# omnibothub-power-two.net
KiCad netlist of a schematic drawn in Altium Designer
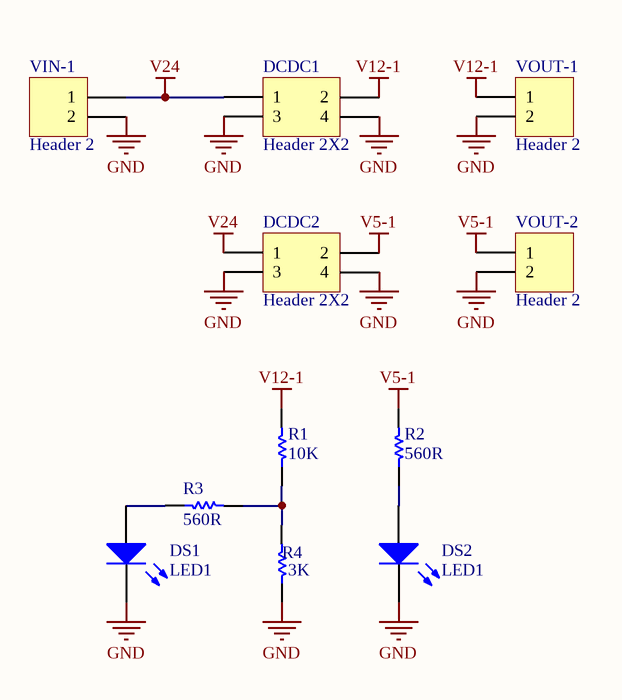
[diagram p0: omnibothub-power-two.SchDoc]

(export (version "E")
  (design (tool "Eeschema 10.0.6"))
  (components
    (comp (ref "DCDC1")
      (value "Header 2X2")
      (footprint "DCDC-1")
      (description "Header, 2-Pin, Dual row")
      (fields (field (name "PUBLISHER") "Altium Limited"))
      (libsource (lib "Miscellaneous Connectors") (part "Header 2X2"))
    )
    (comp (ref "DCDC2")
      (value "Header 2X2")
      (footprint "DCDC-1")
      (description "Header, 2-Pin, Dual row")
      (fields (field (name "PUBLISHER") "Altium Limited"))
      (libsource (lib "Miscellaneous Connectors") (part "Header 2X2"))
    )
    (comp (ref "DS1")
      (value "LED1")
      (footprint "SMDLED")
      (description "Typical RED, GREEN, YELLOW, AMBER GaAs LED")
      (fields (field (name "PUBLISHER") "Altium Limited"))
      (libsource (lib "EXPLORER") (part "LED2"))
    )
    (comp (ref "DS2")
      (value "LED1")
      (footprint "SMDLED")
      (description "Typical RED, GREEN, YELLOW, AMBER GaAs LED")
      (fields (field (name "PUBLISHER") "Altium Limited"))
      (libsource (lib "EXPLORER") (part "LED2"))
    )
    (comp (ref "R1")
      (value "10K")
      (footprint "R0805")
      (description "0603")
      (libsource (lib "stm32f429i") (part "Res2"))
    )
    (comp (ref "R2")
      (value "560R")
      (footprint "R0603")
      (description "0603")
      (libsource (lib "") (part "Res2_1"))
    )
    (comp (ref "R3")
      (value "560R")
      (footprint "R0603")
      (description "0603")
      (libsource (lib "stm32f429i") (part "Res2"))
    )
    (comp (ref "R4")
      (value "3K")
      (footprint "R0805")
      (description "0603")
      (libsource (lib "stm32f429i") (part "Res2"))
    )
    (comp (ref "VIN-1")
      (value "Header 2")
      (footprint "AMASS-XT30PW-M")
      (description "Header, 2-Pin")
      (fields (field (name "PUBLISHER") "Altium Limited"))
      (libsource (lib "") (part "Header 2_1"))
    )
    (comp (ref "VOUT-1")
      (value "Header 2")
      (footprint "AMASS-XT30PW-M")
      (description "Header, 2-Pin")
      (fields (field (name "PUBLISHER") "Altium Limited"))
      (libsource (lib "Miscellaneous Connectors") (part "Header 2"))
    )
    (comp (ref "VOUT-2")
      (value "Header 2")
      (footprint "AMASS-XT30PW-M")
      (description "Header, 2-Pin")
      (fields (field (name "PUBLISHER") "Altium Limited"))
      (libsource (lib "Miscellaneous Connectors") (part "Header 2"))
    )
  )
  (nets
    (net (code "1") (name "GND") (class "Default")
      (node (ref "DCDC1") (pin "3") (pinfunction "3_3") (pintype "passive"))
      (node (ref "DCDC1") (pin "4") (pinfunction "4_4") (pintype "passive"))
      (node (ref "DCDC2") (pin "3") (pinfunction "3_3") (pintype "passive"))
      (node (ref "DCDC2") (pin "4") (pinfunction "4_4") (pintype "passive"))
      (node (ref "DS1") (pin "2") (pinfunction "K_2") (pintype "passive"))
      (node (ref "DS2") (pin "2") (pinfunction "K_2") (pintype "passive"))
      (node (ref "R4") (pin "1") (pinfunction "1_1") (pintype "passive"))
      (node (ref "VIN-1") (pin "2") (pinfunction "2_2") (pintype "passive"))
      (node (ref "VOUT-1") (pin "2") (pinfunction "2_2") (pintype "passive"))
      (node (ref "VOUT-2") (pin "2") (pinfunction "2_2") (pintype "passive"))
    )
    (net (code "2") (name "Net-(DS1-A)") (class "Default")
      (node (ref "DS1") (pin "1") (pinfunction "A_1") (pintype "passive"))
      (node (ref "R3") (pin "1") (pinfunction "1_1") (pintype "passive"))
    )
    (net (code "3") (name "Net-(DS2-A)") (class "Default")
      (node (ref "DS2") (pin "1") (pinfunction "A_1") (pintype "passive"))
      (node (ref "R2") (pin "1") (pinfunction "1_1") (pintype "passive"))
    )
    (net (code "4") (name "Net-(R1-Pad1)") (class "Default")
      (node (ref "R1") (pin "1") (pinfunction "1_1") (pintype "passive"))
      (node (ref "R3") (pin "2") (pinfunction "2_2") (pintype "passive"))
      (node (ref "R4") (pin "2") (pinfunction "2_2") (pintype "passive"))
    )
    (net (code "5") (name "V5-1") (class "Default")
      (node (ref "DCDC2") (pin "2") (pinfunction "2_2") (pintype "passive"))
      (node (ref "R2") (pin "2") (pinfunction "2_2") (pintype "passive"))
      (node (ref "VOUT-2") (pin "1") (pinfunction "1_1") (pintype "passive"))
    )
    (net (code "6") (name "V12-1") (class "Default")
      (node (ref "DCDC1") (pin "2") (pinfunction "2_2") (pintype "passive"))
      (node (ref "R1") (pin "2") (pinfunction "2_2") (pintype "passive"))
      (node (ref "VOUT-1") (pin "1") (pinfunction "1_1") (pintype "passive"))
    )
    (net (code "7") (name "V24") (class "Default")
      (node (ref "DCDC1") (pin "1") (pinfunction "1_1") (pintype "passive"))
      (node (ref "DCDC2") (pin "1") (pinfunction "1_1") (pintype "passive"))
      (node (ref "VIN-1") (pin "1") (pinfunction "1_1") (pintype "passive"))
    )
  )
)
